# Clockv2.net
KiCad netlist of a schematic drawn in EAGLE
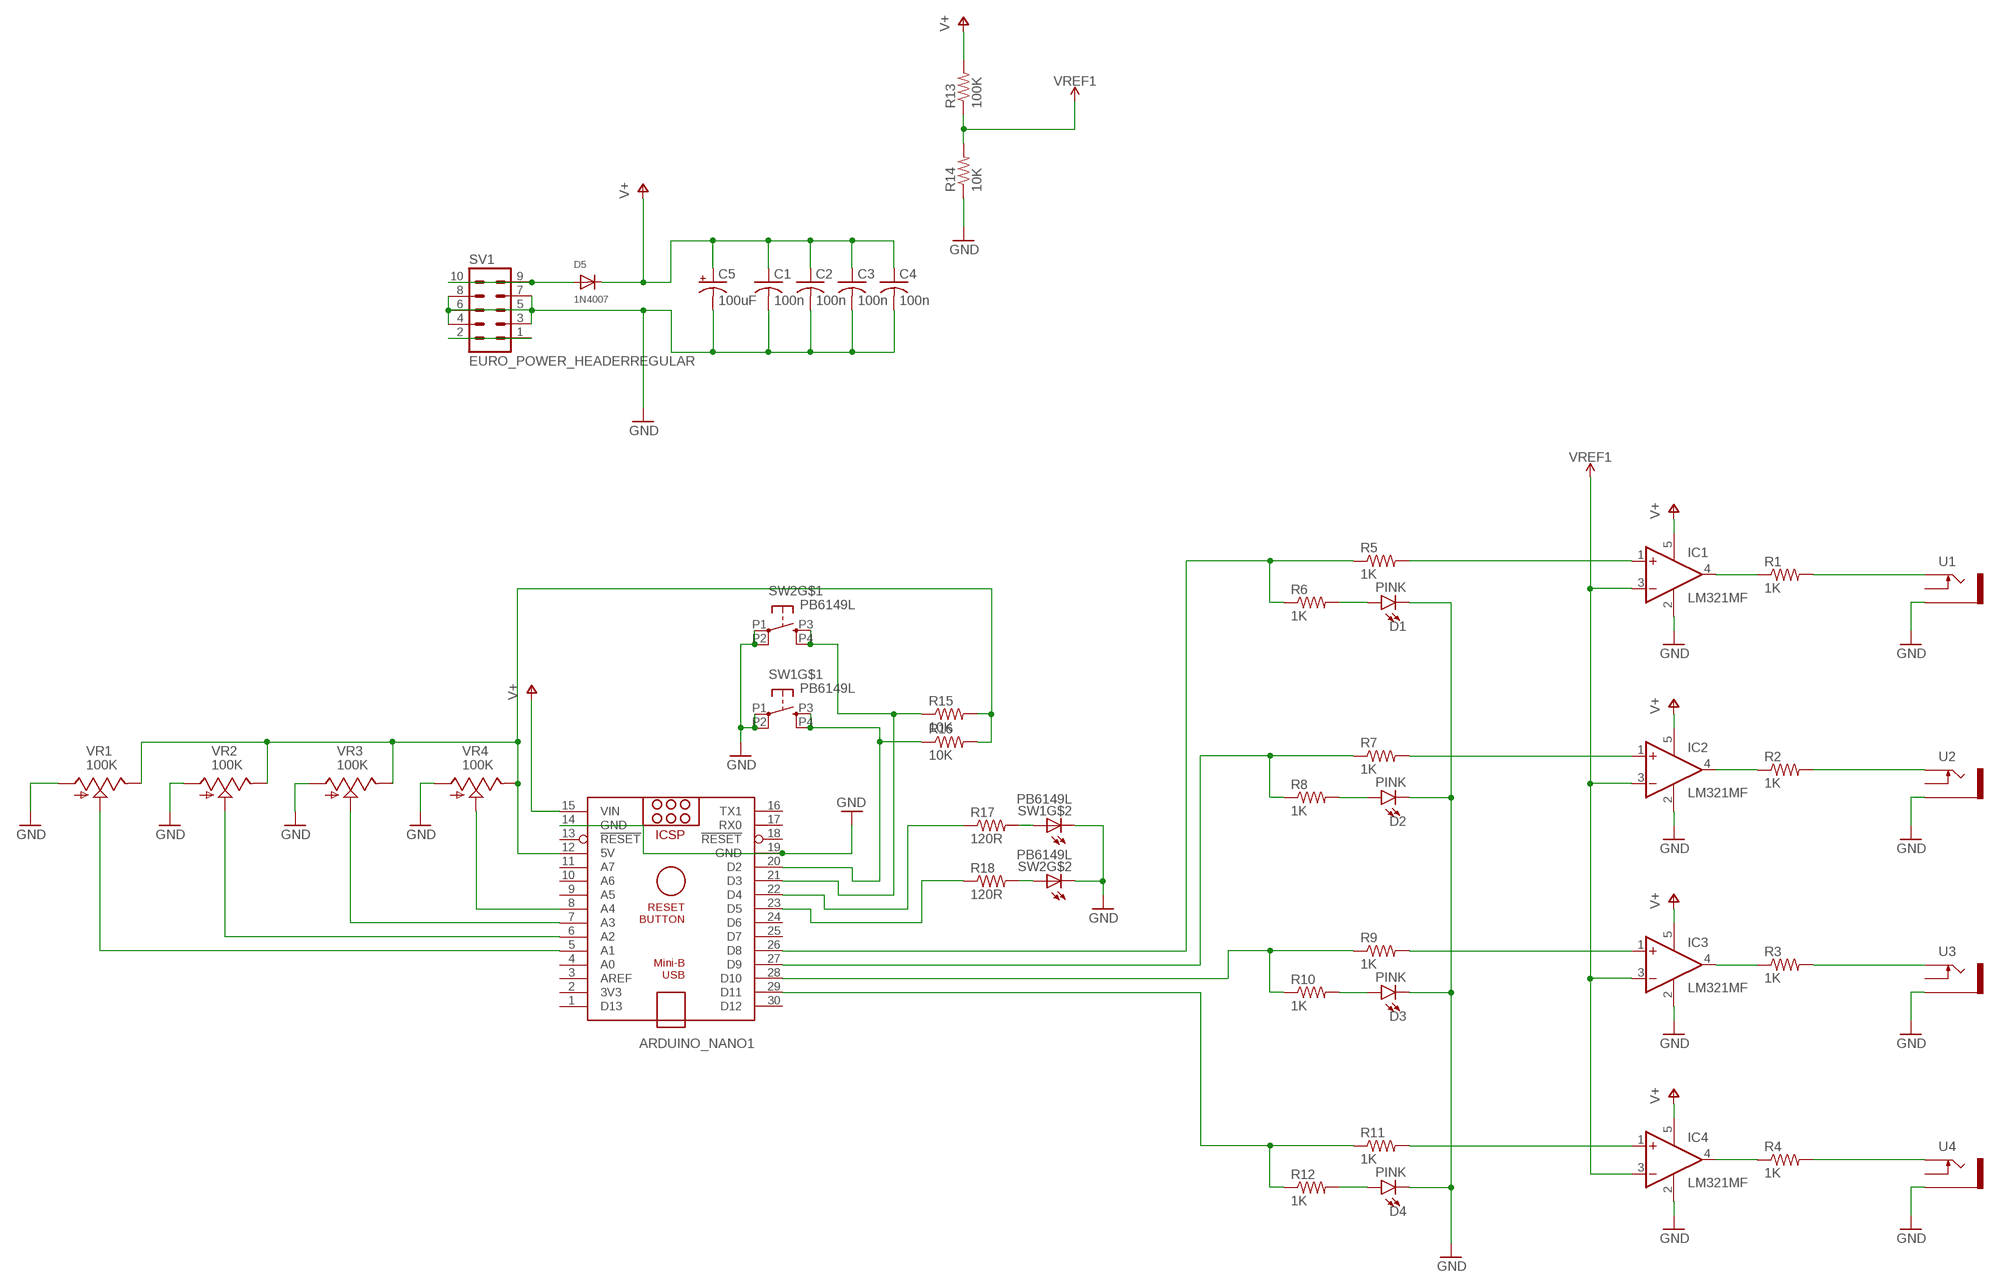
[diagram p0: schematic, sheet 1]

(export (version "E")
  (design (tool "Eeschema 10.0.6"))
  (components
    (comp (ref "ARDUINO_NANO1")
      (value "ARDUINO_NANO")
      (footprint "eagle-import:ARDUINO_NANO")
      (libsource (lib "eagle-import") (part "ARDUINO_NANO"))
    )
    (comp (ref "C1")
      (value "100n")
      (footprint "eagle-import:C0805K")
      (libsource (lib "eagle-import") (part "C-USC0805K"))
    )
    (comp (ref "C2")
      (value "100n")
      (footprint "eagle-import:C0805K")
      (libsource (lib "eagle-import") (part "C-USC0805K"))
    )
    (comp (ref "C3")
      (value "100n")
      (footprint "eagle-import:C0805K")
      (libsource (lib "eagle-import") (part "C-USC0805K"))
    )
    (comp (ref "C4")
      (value "100n")
      (footprint "eagle-import:C0805K")
      (libsource (lib "eagle-import") (part "C-USC0805K"))
    )
    (comp (ref "C5")
      (value "100uF")
      (footprint "eagle-import:PANASONIC_B")
      (libsource (lib "eagle-import") (part "CPOL-USB"))
    )
    (comp (ref "D1")
      (value "PINK")
      (footprint "eagle-import:LED_3MM")
      (libsource (lib "eagle-import") (part "LED3MM"))
    )
    (comp (ref "D2")
      (value "PINK")
      (footprint "eagle-import:LED_3MM")
      (libsource (lib "eagle-import") (part "LED3MM"))
    )
    (comp (ref "D3")
      (value "PINK")
      (footprint "eagle-import:LED_3MM")
      (libsource (lib "eagle-import") (part "LED3MM"))
    )
    (comp (ref "D4")
      (value "PINK")
      (footprint "eagle-import:LED_3MM")
      (libsource (lib "eagle-import") (part "LED3MM"))
    )
    (comp (ref "D5")
      (value "1N4007")
      (footprint "eagle-import:SOD-123")
      (libsource (lib "eagle-import") (part "DIODESOD-123"))
    )
    (comp (ref "IC1")
      (value "LM321MF")
      (footprint "eagle-import:SOT23-5")
      (libsource (lib "eagle-import") (part "LM321?MF"))
    )
    (comp (ref "IC2")
      (value "LM321MF")
      (footprint "eagle-import:SOT23-5")
      (libsource (lib "eagle-import") (part "LM321?MF"))
    )
    (comp (ref "IC3")
      (value "LM321MF")
      (footprint "eagle-import:SOT23-5")
      (libsource (lib "eagle-import") (part "LM321?MF"))
    )
    (comp (ref "IC4")
      (value "LM321MF")
      (footprint "eagle-import:SOT23-5")
      (libsource (lib "eagle-import") (part "LM321?MF"))
    )
    (comp (ref "R1")
      (value "1K")
      (footprint "eagle-import:R0805")
      (libsource (lib "eagle-import") (part "R-US_R0805"))
    )
    (comp (ref "R2")
      (value "1K")
      (footprint "eagle-import:R0805")
      (libsource (lib "eagle-import") (part "R-US_R0805"))
    )
    (comp (ref "R3")
      (value "1K")
      (footprint "eagle-import:R0805")
      (libsource (lib "eagle-import") (part "R-US_R0805"))
    )
    (comp (ref "R4")
      (value "1K")
      (footprint "eagle-import:R0805")
      (libsource (lib "eagle-import") (part "R-US_R0805"))
    )
    (comp (ref "R5")
      (value "1K")
      (footprint "eagle-import:R0805")
      (libsource (lib "eagle-import") (part "R-US_R0805"))
    )
    (comp (ref "R6")
      (value "1K")
      (footprint "eagle-import:R0805")
      (libsource (lib "eagle-import") (part "R-US_R0805"))
    )
    (comp (ref "R7")
      (value "1K")
      (footprint "eagle-import:R0805")
      (libsource (lib "eagle-import") (part "R-US_R0805"))
    )
    (comp (ref "R8")
      (value "1K")
      (footprint "eagle-import:R0805")
      (libsource (lib "eagle-import") (part "R-US_R0805"))
    )
    (comp (ref "R9")
      (value "1K")
      (footprint "eagle-import:R0805")
      (libsource (lib "eagle-import") (part "R-US_R0805"))
    )
    (comp (ref "R10")
      (value "1K")
      (footprint "eagle-import:R0805")
      (libsource (lib "eagle-import") (part "R-US_R0805"))
    )
    (comp (ref "R11")
      (value "1K")
      (footprint "eagle-import:R0805")
      (libsource (lib "eagle-import") (part "R-US_R0805"))
    )
    (comp (ref "R12")
      (value "1K")
      (footprint "eagle-import:R0805")
      (libsource (lib "eagle-import") (part "R-US_R0805"))
    )
    (comp (ref "R13")
      (value "100K")
      (footprint "eagle-import:R0805")
      (libsource (lib "eagle-import") (part "R-US_R0805"))
    )
    (comp (ref "R14")
      (value "10K")
      (footprint "eagle-import:R0805")
      (libsource (lib "eagle-import") (part "R-US_R0805"))
    )
    (comp (ref "R15")
      (value "10K")
      (footprint "eagle-import:R0805")
      (libsource (lib "eagle-import") (part "R-US_R0805"))
    )
    (comp (ref "R16")
      (value "10K")
      (footprint "eagle-import:R0805")
      (libsource (lib "eagle-import") (part "R-US_R0805"))
    )
    (comp (ref "R17")
      (value "120R")
      (footprint "eagle-import:R0805")
      (libsource (lib "eagle-import") (part "R-US_R0805"))
    )
    (comp (ref "R18")
      (value "120R")
      (footprint "eagle-import:R0805")
      (libsource (lib "eagle-import") (part "R-US_R0805"))
    )
    (comp (ref "SV1")
      (value "EURO_POWER_HEADERREGULAR")
      (footprint "eagle-import:EURO_POWER_HEADER")
      (libsource (lib "eagle-import") (part "EURO_POWER_HEADERREGULAR"))
    )
    (comp (ref "SW1")
      (value "PB6149L")
      (footprint "eagle-import:PB6149L")
      (libsource (lib "eagle-import") (part "PB6149L"))
    )
    (comp (ref "SW2")
      (value "PB6149L")
      (footprint "eagle-import:PB6149L")
      (libsource (lib "eagle-import") (part "PB6149L"))
    )
    (comp (ref "U1")
      (value "THONKICONNNEW")
      (footprint "eagle-import:WQP-PJ301M-12_JACK")
      (libsource (lib "eagle-import") (part "THONKICONNNEW"))
    )
    (comp (ref "U2")
      (value "THONKICONNNEW")
      (footprint "eagle-import:WQP-PJ301M-12_JACK")
      (libsource (lib "eagle-import") (part "THONKICONNNEW"))
    )
    (comp (ref "U3")
      (value "THONKICONNNEW")
      (footprint "eagle-import:WQP-PJ301M-12_JACK")
      (libsource (lib "eagle-import") (part "THONKICONNNEW"))
    )
    (comp (ref "U4")
      (value "THONKICONNNEW")
      (footprint "eagle-import:WQP-PJ301M-12_JACK")
      (libsource (lib "eagle-import") (part "THONKICONNNEW"))
    )
    (comp (ref "VR1")
      (value "100K")
      (footprint "eagle-import:9MM_SNAP-IN_POT")
      (libsource (lib "eagle-import") (part "9MM_SNAP-IN_POT_"))
    )
    (comp (ref "VR2")
      (value "100K")
      (footprint "eagle-import:9MM_SNAP-IN_POT")
      (libsource (lib "eagle-import") (part "9MM_SNAP-IN_POT_"))
    )
    (comp (ref "VR3")
      (value "100K")
      (footprint "eagle-import:9MM_SNAP-IN_POT")
      (libsource (lib "eagle-import") (part "9MM_SNAP-IN_POT_"))
    )
    (comp (ref "VR4")
      (value "100K")
      (footprint "eagle-import:9MM_SNAP-IN_POT")
      (libsource (lib "eagle-import") (part "9MM_SNAP-IN_POT_"))
    )
  )
  (nets
    (net (code "1") (name "GND") (class "Default")
      (node (ref "ARDUINO_NANO1") (pin "14") (pinfunction "GND_14") (pintype "power_in"))
      (node (ref "ARDUINO_NANO1") (pin "19") (pinfunction "GND_19") (pintype "power_in"))
      (node (ref "C1") (pin "2") (pinfunction "2_2") (pintype "passive"))
      (node (ref "C2") (pin "2") (pinfunction "2_2") (pintype "passive"))
      (node (ref "C3") (pin "2") (pinfunction "2_2") (pintype "passive"))
      (node (ref "C4") (pin "2") (pinfunction "2_2") (pintype "passive"))
      (node (ref "C5") (pin "-") (pinfunction "-_-") (pintype "passive"))
      (node (ref "D1") (pin "K") (pinfunction "C_K") (pintype "passive"))
      (node (ref "D2") (pin "K") (pinfunction "C_K") (pintype "passive"))
      (node (ref "D3") (pin "K") (pinfunction "C_K") (pintype "passive"))
      (node (ref "D4") (pin "K") (pinfunction "C_K") (pintype "passive"))
      (node (ref "IC1") (pin "2") (pinfunction "V-_2") (pintype "power_in"))
      (node (ref "IC2") (pin "2") (pinfunction "V-_2") (pintype "power_in"))
      (node (ref "IC3") (pin "2") (pinfunction "V-_2") (pintype "power_in"))
      (node (ref "IC4") (pin "2") (pinfunction "V-_2") (pintype "power_in"))
      (node (ref "R14") (pin "1") (pinfunction "1_1") (pintype "passive"))
      (node (ref "SV1") (pin "3") (pinfunction "3_3") (pintype "passive"))
      (node (ref "SV1") (pin "4") (pinfunction "4_4") (pintype "passive"))
      (node (ref "SV1") (pin "5") (pinfunction "5_5") (pintype "passive"))
      (node (ref "SV1") (pin "6") (pinfunction "6_6") (pintype "passive"))
      (node (ref "SV1") (pin "7") (pinfunction "7_7") (pintype "passive"))
      (node (ref "SV1") (pin "8") (pinfunction "8_8") (pintype "passive"))
      (node (ref "SW1") (pin "L2") (pinfunction "C_L2") (pintype "passive"))
      (node (ref "SW1") (pin "P1") (pinfunction "P_P1") (pintype "passive"))
      (node (ref "SW1") (pin "P2") (pinfunction "P1_P2") (pintype "passive"))
      (node (ref "SW2") (pin "L2") (pinfunction "C_L2") (pintype "passive"))
      (node (ref "SW2") (pin "P1") (pinfunction "P_P1") (pintype "passive"))
      (node (ref "SW2") (pin "P2") (pinfunction "P1_P2") (pintype "passive"))
      (node (ref "U1") (pin "P$3_SLEEVE") (pinfunction "SLEEVE_P$3_SLEEVE") (pintype "passive"))
      (node (ref "U2") (pin "P$3_SLEEVE") (pinfunction "SLEEVE_P$3_SLEEVE") (pintype "passive"))
      (node (ref "U3") (pin "P$3_SLEEVE") (pinfunction "SLEEVE_P$3_SLEEVE") (pintype "passive"))
      (node (ref "U4") (pin "P$3_SLEEVE") (pinfunction "SLEEVE_P$3_SLEEVE") (pintype "passive"))
      (node (ref "VR1") (pin "1") (pinfunction "A_1") (pintype "passive"))
      (node (ref "VR2") (pin "1") (pinfunction "A_1") (pintype "passive"))
      (node (ref "VR3") (pin "1") (pinfunction "A_1") (pintype "passive"))
      (node (ref "VR4") (pin "1") (pinfunction "A_1") (pintype "passive"))
    )
    (net (code "2") (name "Net-(ARDUINO_NANO1-5V)") (class "Default")
      (node (ref "ARDUINO_NANO1") (pin "12") (pinfunction "5V_12") (pintype "power_in"))
      (node (ref "R15") (pin "2") (pinfunction "2_2") (pintype "passive"))
      (node (ref "R16") (pin "2") (pinfunction "2_2") (pintype "passive"))
      (node (ref "VR1") (pin "3") (pinfunction "E_3") (pintype "passive"))
      (node (ref "VR2") (pin "3") (pinfunction "E_3") (pintype "passive"))
      (node (ref "VR3") (pin "3") (pinfunction "E_3") (pintype "passive"))
      (node (ref "VR4") (pin "3") (pinfunction "E_3") (pintype "passive"))
    )
    (net (code "3") (name "Net-(ARDUINO_NANO1-A1)") (class "Default")
      (node (ref "ARDUINO_NANO1") (pin "5") (pinfunction "A1_5") (pintype "bidirectional"))
      (node (ref "VR1") (pin "2") (pinfunction "S_2") (pintype "passive"))
    )
    (net (code "4") (name "Net-(ARDUINO_NANO1-A2)") (class "Default")
      (node (ref "ARDUINO_NANO1") (pin "6") (pinfunction "A2_6") (pintype "bidirectional"))
      (node (ref "VR2") (pin "2") (pinfunction "S_2") (pintype "passive"))
    )
    (net (code "5") (name "Net-(ARDUINO_NANO1-A3)") (class "Default")
      (node (ref "ARDUINO_NANO1") (pin "7") (pinfunction "A3_7") (pintype "bidirectional"))
      (node (ref "VR3") (pin "2") (pinfunction "S_2") (pintype "passive"))
    )
    (net (code "6") (name "Net-(ARDUINO_NANO1-A4)") (class "Default")
      (node (ref "ARDUINO_NANO1") (pin "8") (pinfunction "A4_8") (pintype "bidirectional"))
      (node (ref "VR4") (pin "2") (pinfunction "S_2") (pintype "passive"))
    )
    (net (code "7") (name "Net-(ARDUINO_NANO1-D2)") (class "Default")
      (node (ref "ARDUINO_NANO1") (pin "20") (pinfunction "D2_20") (pintype "bidirectional"))
      (node (ref "R16") (pin "1") (pinfunction "1_1") (pintype "passive"))
      (node (ref "SW1") (pin "P3") (pinfunction "S_P3") (pintype "passive"))
      (node (ref "SW1") (pin "P4") (pinfunction "S1_P4") (pintype "passive"))
    )
    (net (code "8") (name "Net-(ARDUINO_NANO1-D3)") (class "Default")
      (node (ref "ARDUINO_NANO1") (pin "21") (pinfunction "D3_21") (pintype "bidirectional"))
      (node (ref "R15") (pin "1") (pinfunction "1_1") (pintype "passive"))
      (node (ref "SW2") (pin "P3") (pinfunction "S_P3") (pintype "passive"))
      (node (ref "SW2") (pin "P4") (pinfunction "S1_P4") (pintype "passive"))
    )
    (net (code "9") (name "Net-(ARDUINO_NANO1-D4)") (class "Default")
      (node (ref "ARDUINO_NANO1") (pin "22") (pinfunction "D4_22") (pintype "bidirectional"))
      (node (ref "R17") (pin "1") (pinfunction "1_1") (pintype "passive"))
    )
    (net (code "10") (name "Net-(ARDUINO_NANO1-D5)") (class "Default")
      (node (ref "ARDUINO_NANO1") (pin "23") (pinfunction "D5_23") (pintype "bidirectional"))
      (node (ref "R18") (pin "1") (pinfunction "1_1") (pintype "passive"))
    )
    (net (code "11") (name "Net-(ARDUINO_NANO1-D8)") (class "Default")
      (node (ref "ARDUINO_NANO1") (pin "26") (pinfunction "D8_26") (pintype "bidirectional"))
      (node (ref "R5") (pin "1") (pinfunction "1_1") (pintype "passive"))
      (node (ref "R6") (pin "1") (pinfunction "1_1") (pintype "passive"))
    )
    (net (code "12") (name "Net-(ARDUINO_NANO1-D9)") (class "Default")
      (node (ref "ARDUINO_NANO1") (pin "27") (pinfunction "D9_27") (pintype "bidirectional"))
      (node (ref "R7") (pin "1") (pinfunction "1_1") (pintype "passive"))
      (node (ref "R8") (pin "1") (pinfunction "1_1") (pintype "passive"))
    )
    (net (code "13") (name "Net-(ARDUINO_NANO1-D10)") (class "Default")
      (node (ref "ARDUINO_NANO1") (pin "28") (pinfunction "D10_28") (pintype "bidirectional"))
      (node (ref "R10") (pin "1") (pinfunction "1_1") (pintype "passive"))
      (node (ref "R9") (pin "1") (pinfunction "1_1") (pintype "passive"))
    )
    (net (code "14") (name "Net-(ARDUINO_NANO1-D11)") (class "Default")
      (node (ref "ARDUINO_NANO1") (pin "29") (pinfunction "D11_29") (pintype "bidirectional"))
      (node (ref "R11") (pin "1") (pinfunction "1_1") (pintype "passive"))
      (node (ref "R12") (pin "1") (pinfunction "1_1") (pintype "passive"))
    )
    (net (code "15") (name "Net-(D1-PadA)") (class "Default")
      (node (ref "D1") (pin "A") (pinfunction "A_A") (pintype "passive"))
      (node (ref "R6") (pin "2") (pinfunction "2_2") (pintype "passive"))
    )
    (net (code "16") (name "Net-(D2-PadA)") (class "Default")
      (node (ref "D2") (pin "A") (pinfunction "A_A") (pintype "passive"))
      (node (ref "R8") (pin "2") (pinfunction "2_2") (pintype "passive"))
    )
    (net (code "17") (name "Net-(D3-PadA)") (class "Default")
      (node (ref "D3") (pin "A") (pinfunction "A_A") (pintype "passive"))
      (node (ref "R10") (pin "2") (pinfunction "2_2") (pintype "passive"))
    )
    (net (code "18") (name "Net-(D4-PadA)") (class "Default")
      (node (ref "D4") (pin "A") (pinfunction "A_A") (pintype "passive"))
      (node (ref "R12") (pin "2") (pinfunction "2_2") (pintype "passive"))
    )
    (net (code "19") (name "Net-(D5-PadA)") (class "Default")
      (node (ref "D5") (pin "A") (pinfunction "A_A") (pintype "passive"))
      (node (ref "SV1") (pin "10") (pinfunction "10_10") (pintype "passive"))
      (node (ref "SV1") (pin "9") (pinfunction "9_9") (pintype "passive"))
    )
    (net (code "20") (name "Net-(IC1-+IN)") (class "Default")
      (node (ref "IC1") (pin "1") (pinfunction "+IN_1") (pintype "input"))
      (node (ref "R5") (pin "2") (pinfunction "2_2") (pintype "passive"))
    )
    (net (code "21") (name "Net-(IC1-OUT)") (class "Default")
      (node (ref "IC1") (pin "4") (pinfunction "OUT_4") (pintype "output"))
      (node (ref "R1") (pin "1") (pinfunction "1_1") (pintype "passive"))
    )
    (net (code "22") (name "Net-(IC2-+IN)") (class "Default")
      (node (ref "IC2") (pin "1") (pinfunction "+IN_1") (pintype "input"))
      (node (ref "R7") (pin "2") (pinfunction "2_2") (pintype "passive"))
    )
    (net (code "23") (name "Net-(IC2-OUT)") (class "Default")
      (node (ref "IC2") (pin "4") (pinfunction "OUT_4") (pintype "output"))
      (node (ref "R2") (pin "1") (pinfunction "1_1") (pintype "passive"))
    )
    (net (code "24") (name "Net-(IC3-+IN)") (class "Default")
      (node (ref "IC3") (pin "1") (pinfunction "+IN_1") (pintype "input"))
      (node (ref "R9") (pin "2") (pinfunction "2_2") (pintype "passive"))
    )
    (net (code "25") (name "Net-(IC3-OUT)") (class "Default")
      (node (ref "IC3") (pin "4") (pinfunction "OUT_4") (pintype "output"))
      (node (ref "R3") (pin "1") (pinfunction "1_1") (pintype "passive"))
    )
    (net (code "26") (name "Net-(IC4-+IN)") (class "Default")
      (node (ref "IC4") (pin "1") (pinfunction "+IN_1") (pintype "input"))
      (node (ref "R11") (pin "2") (pinfunction "2_2") (pintype "passive"))
    )
    (net (code "27") (name "Net-(IC4-OUT)") (class "Default")
      (node (ref "IC4") (pin "4") (pinfunction "OUT_4") (pintype "output"))
      (node (ref "R4") (pin "1") (pinfunction "1_1") (pintype "passive"))
    )
    (net (code "28") (name "Net-(SV1-Pad1)") (class "Default")
      (node (ref "SV1") (pin "1") (pinfunction "1_1") (pintype "passive"))
      (node (ref "SV1") (pin "2") (pinfunction "2_2") (pintype "passive"))
    )
    (net (code "29") (name "Net-(SW1B-A)") (class "Default")
      (node (ref "R17") (pin "2") (pinfunction "2_2") (pintype "passive"))
      (node (ref "SW1") (pin "L1") (pinfunction "A_L1") (pintype "passive"))
    )
    (net (code "30") (name "Net-(SW2B-A)") (class "Default")
      (node (ref "R18") (pin "2") (pinfunction "2_2") (pintype "passive"))
      (node (ref "SW2") (pin "L1") (pinfunction "A_L1") (pintype "passive"))
    )
    (net (code "31") (name "Net-(U1-TIP)") (class "Default")
      (node (ref "R1") (pin "2") (pinfunction "2_2") (pintype "passive"))
      (node (ref "U1") (pin "P$1_TIP") (pinfunction "TIP_P$1_TIP") (pintype "passive"))
    )
    (net (code "32") (name "Net-(U2-TIP)") (class "Default")
      (node (ref "R2") (pin "2") (pinfunction "2_2") (pintype "passive"))
      (node (ref "U2") (pin "P$1_TIP") (pinfunction "TIP_P$1_TIP") (pintype "passive"))
    )
    (net (code "33") (name "Net-(U3-TIP)") (class "Default")
      (node (ref "R3") (pin "2") (pinfunction "2_2") (pintype "passive"))
      (node (ref "U3") (pin "P$1_TIP") (pinfunction "TIP_P$1_TIP") (pintype "passive"))
    )
    (net (code "34") (name "Net-(U4-TIP)") (class "Default")
      (node (ref "R4") (pin "2") (pinfunction "2_2") (pintype "passive"))
      (node (ref "U4") (pin "P$1_TIP") (pinfunction "TIP_P$1_TIP") (pintype "passive"))
    )
    (net (code "35") (name "V+") (class "Default")
      (node (ref "ARDUINO_NANO1") (pin "15") (pinfunction "VIN_15") (pintype "power_in"))
      (node (ref "C1") (pin "1") (pinfunction "1_1") (pintype "passive"))
      (node (ref "C2") (pin "1") (pinfunction "1_1") (pintype "passive"))
      (node (ref "C3") (pin "1") (pinfunction "1_1") (pintype "passive"))
      (node (ref "C4") (pin "1") (pinfunction "1_1") (pintype "passive"))
      (node (ref "C5") (pin "+") (pinfunction "+_+") (pintype "passive"))
      (node (ref "D5") (pin "C") (pinfunction "C_C") (pintype "passive"))
      (node (ref "IC1") (pin "5") (pinfunction "V+_5") (pintype "power_in"))
      (node (ref "IC2") (pin "5") (pinfunction "V+_5") (pintype "power_in"))
      (node (ref "IC3") (pin "5") (pinfunction "V+_5") (pintype "power_in"))
      (node (ref "IC4") (pin "5") (pinfunction "V+_5") (pintype "power_in"))
      (node (ref "R13") (pin "2") (pinfunction "2_2") (pintype "passive"))
    )
    (net (code "36") (name "VREF1") (class "Default")
      (node (ref "IC1") (pin "3") (pinfunction "-IN_3") (pintype "input"))
      (node (ref "IC2") (pin "3") (pinfunction "-IN_3") (pintype "input"))
      (node (ref "IC3") (pin "3") (pinfunction "-IN_3") (pintype "input"))
      (node (ref "IC4") (pin "3") (pinfunction "-IN_3") (pintype "input"))
      (node (ref "R13") (pin "1") (pinfunction "1_1") (pintype "passive"))
      (node (ref "R14") (pin "2") (pinfunction "2_2") (pintype "passive"))
    )
    (net (code "37") (name "unconnected-(ARDUINO_NANO1-3V3-Pad2)") (class "Default")
      (node (ref "ARDUINO_NANO1") (pin "2") (pinfunction "3V3_2") (pintype "output"))
    )
    (net (code "38") (name "unconnected-(ARDUINO_NANO1-A0-Pad4)") (class "Default")
      (node (ref "ARDUINO_NANO1") (pin "4") (pinfunction "A0_4") (pintype "bidirectional"))
    )
    (net (code "39") (name "unconnected-(ARDUINO_NANO1-A5-Pad9)") (class "Default")
      (node (ref "ARDUINO_NANO1") (pin "9") (pinfunction "A5_9") (pintype "bidirectional"))
    )
    (net (code "40") (name "unconnected-(ARDUINO_NANO1-A6-Pad10)") (class "Default")
      (node (ref "ARDUINO_NANO1") (pin "10") (pinfunction "A6_10") (pintype "bidirectional"))
    )
    (net (code "41") (name "unconnected-(ARDUINO_NANO1-A7-Pad11)") (class "Default")
      (node (ref "ARDUINO_NANO1") (pin "11") (pinfunction "A7_11") (pintype "bidirectional"))
    )
    (net (code "42") (name "unconnected-(ARDUINO_NANO1-AREF-Pad3)") (class "Default")
      (node (ref "ARDUINO_NANO1") (pin "3") (pinfunction "AREF_3") (pintype "input"))
    )
    (net (code "43") (name "unconnected-(ARDUINO_NANO1-D6-Pad24)") (class "Default")
      (node (ref "ARDUINO_NANO1") (pin "24") (pinfunction "D6_24") (pintype "bidirectional"))
    )
    (net (code "44") (name "unconnected-(ARDUINO_NANO1-D7-Pad25)") (class "Default")
      (node (ref "ARDUINO_NANO1") (pin "25") (pinfunction "D7_25") (pintype "bidirectional"))
    )
    (net (code "45") (name "unconnected-(ARDUINO_NANO1-D12-Pad30)") (class "Default")
      (node (ref "ARDUINO_NANO1") (pin "30") (pinfunction "D12_30") (pintype "bidirectional"))
    )
    (net (code "46") (name "unconnected-(ARDUINO_NANO1-D13-Pad1)") (class "Default")
      (node (ref "ARDUINO_NANO1") (pin "1") (pinfunction "D13_1") (pintype "bidirectional"))
    )
    (net (code "47") (name "unconnected-(ARDUINO_NANO1-RX0-Pad17)") (class "Default")
      (node (ref "ARDUINO_NANO1") (pin "17") (pinfunction "RX0_17") (pintype "bidirectional"))
    )
    (net (code "48") (name "unconnected-(ARDUINO_NANO1-TX1-Pad16)") (class "Default")
      (node (ref "ARDUINO_NANO1") (pin "16") (pinfunction "TX1_16") (pintype "bidirectional"))
    )
    (net (code "49") (name "unconnected-(ARDUINO_NANO1-~{RESET}-Pad13)") (class "Default")
      (node (ref "ARDUINO_NANO1") (pin "13") (pinfunction "~{RESET}_13") (pintype "input"))
    )
    (net (code "50") (name "unconnected-(ARDUINO_NANO1-~{RESET}-Pad18)") (class "Default")
      (node (ref "ARDUINO_NANO1") (pin "18") (pinfunction "~{RESET}_18") (pintype "input"))
    )
    (net (code "51") (name "unconnected-(U1-SWITCH-PadP$2_SWITCH)") (class "Default")
      (node (ref "U1") (pin "P$2_SWITCH") (pinfunction "SWITCH_P$2_SWITCH") (pintype "passive"))
    )
    (net (code "52") (name "unconnected-(U2-SWITCH-PadP$2_SWITCH)") (class "Default")
      (node (ref "U2") (pin "P$2_SWITCH") (pinfunction "SWITCH_P$2_SWITCH") (pintype "passive"))
    )
    (net (code "53") (name "unconnected-(U3-SWITCH-PadP$2_SWITCH)") (class "Default")
      (node (ref "U3") (pin "P$2_SWITCH") (pinfunction "SWITCH_P$2_SWITCH") (pintype "passive"))
    )
    (net (code "54") (name "unconnected-(U4-SWITCH-PadP$2_SWITCH)") (class "Default")
      (node (ref "U4") (pin "P$2_SWITCH") (pinfunction "SWITCH_P$2_SWITCH") (pintype "passive"))
    )
  )
)
